# DoubleBoilerPower.net
KiCad netlist of a schematic drawn in EAGLE
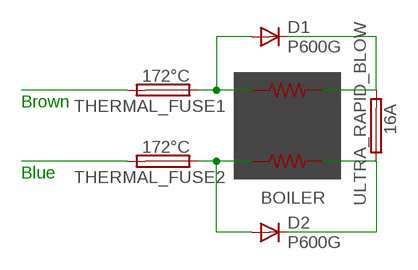
[diagram p0: schematic, sheet 1]

(export (version "E")
  (design (tool "Eeschema 10.0.6"))
  (components
    (comp (ref "100K2")
      (value "R-US_0204/2V")
      (footprint "eagle-import:0204V")
      (libsource (lib "eagle-import") (part "R-US_0204/2V"))
    )
    (comp (ref "BOILER")
      (value "R-US_0204/2V")
      (footprint "eagle-import:0204V")
      (libsource (lib "eagle-import") (part "R-US_0204/2V"))
    )
    (comp (ref "D1")
      (value "P600G")
      (footprint "eagle-import:DO41-10")
      (libsource (lib "eagle-import") (part "1N4004"))
    )
    (comp (ref "D2")
      (value "P600G")
      (footprint "eagle-import:DO41-10")
      (libsource (lib "eagle-import") (part "1N4004"))
    )
    (comp (ref "THERMAL_FUSE1")
      (value "172°C")
      (footprint "eagle-import:19559")
      (fields (field (name "MPN") "55900000001"))
      (libsource (lib "eagle-import") (part "19559"))
    )
    (comp (ref "THERMAL_FUSE2")
      (value "172°C")
      (footprint "eagle-import:19559")
      (fields (field (name "MPN") "55900000001"))
      (libsource (lib "eagle-import") (part "19559"))
    )
    (comp (ref "ULTRA_RAPID_BLOW")
      (value "16A")
      (footprint "eagle-import:19559")
      (fields (field (name "MPN") "55900000001"))
      (libsource (lib "eagle-import") (part "19559"))
    )
  )
  (nets
    (net (code "1") (name "Net-(100K2-Pad1)") (class "Default")
      (node (ref "100K2") (pin "1") (pinfunction "1_1") (pintype "passive"))
      (node (ref "D2") (pin "A") (pinfunction "A_A") (pintype "passive"))
      (node (ref "THERMAL_FUSE2") (pin "1") (pinfunction "1_1") (pintype "passive"))
    )
    (net (code "2") (name "Net-(100K2-Pad2)") (class "Default")
      (node (ref "100K2") (pin "2") (pinfunction "2_2") (pintype "passive"))
      (node (ref "D2") (pin "C") (pinfunction "C_C") (pintype "passive"))
      (node (ref "ULTRA_RAPID_BLOW") (pin "1") (pinfunction "1_1") (pintype "passive"))
    )
    (net (code "3") (name "Net-(BOILER-Pad1)") (class "Default")
      (node (ref "BOILER") (pin "1") (pinfunction "1_1") (pintype "passive"))
      (node (ref "D1") (pin "A") (pinfunction "A_A") (pintype "passive"))
      (node (ref "THERMAL_FUSE1") (pin "1") (pinfunction "1_1") (pintype "passive"))
    )
    (net (code "4") (name "Net-(BOILER-Pad2)") (class "Default")
      (node (ref "BOILER") (pin "2") (pinfunction "2_2") (pintype "passive"))
      (node (ref "D1") (pin "C") (pinfunction "C_C") (pintype "passive"))
      (node (ref "ULTRA_RAPID_BLOW") (pin "2") (pinfunction "2_2") (pintype "passive"))
    )
    (net (code "5") (name "unconnected-(THERMAL_FUSE1-Pad2)") (class "Default")
      (node (ref "THERMAL_FUSE1") (pin "2") (pinfunction "2_2") (pintype "passive"))
    )
    (net (code "6") (name "unconnected-(THERMAL_FUSE2-Pad2)") (class "Default")
      (node (ref "THERMAL_FUSE2") (pin "2") (pinfunction "2_2") (pintype "passive"))
    )
  )
)
